# PD_Regulator.net
KiCad netlist of a schematic drawn in Altium Designer
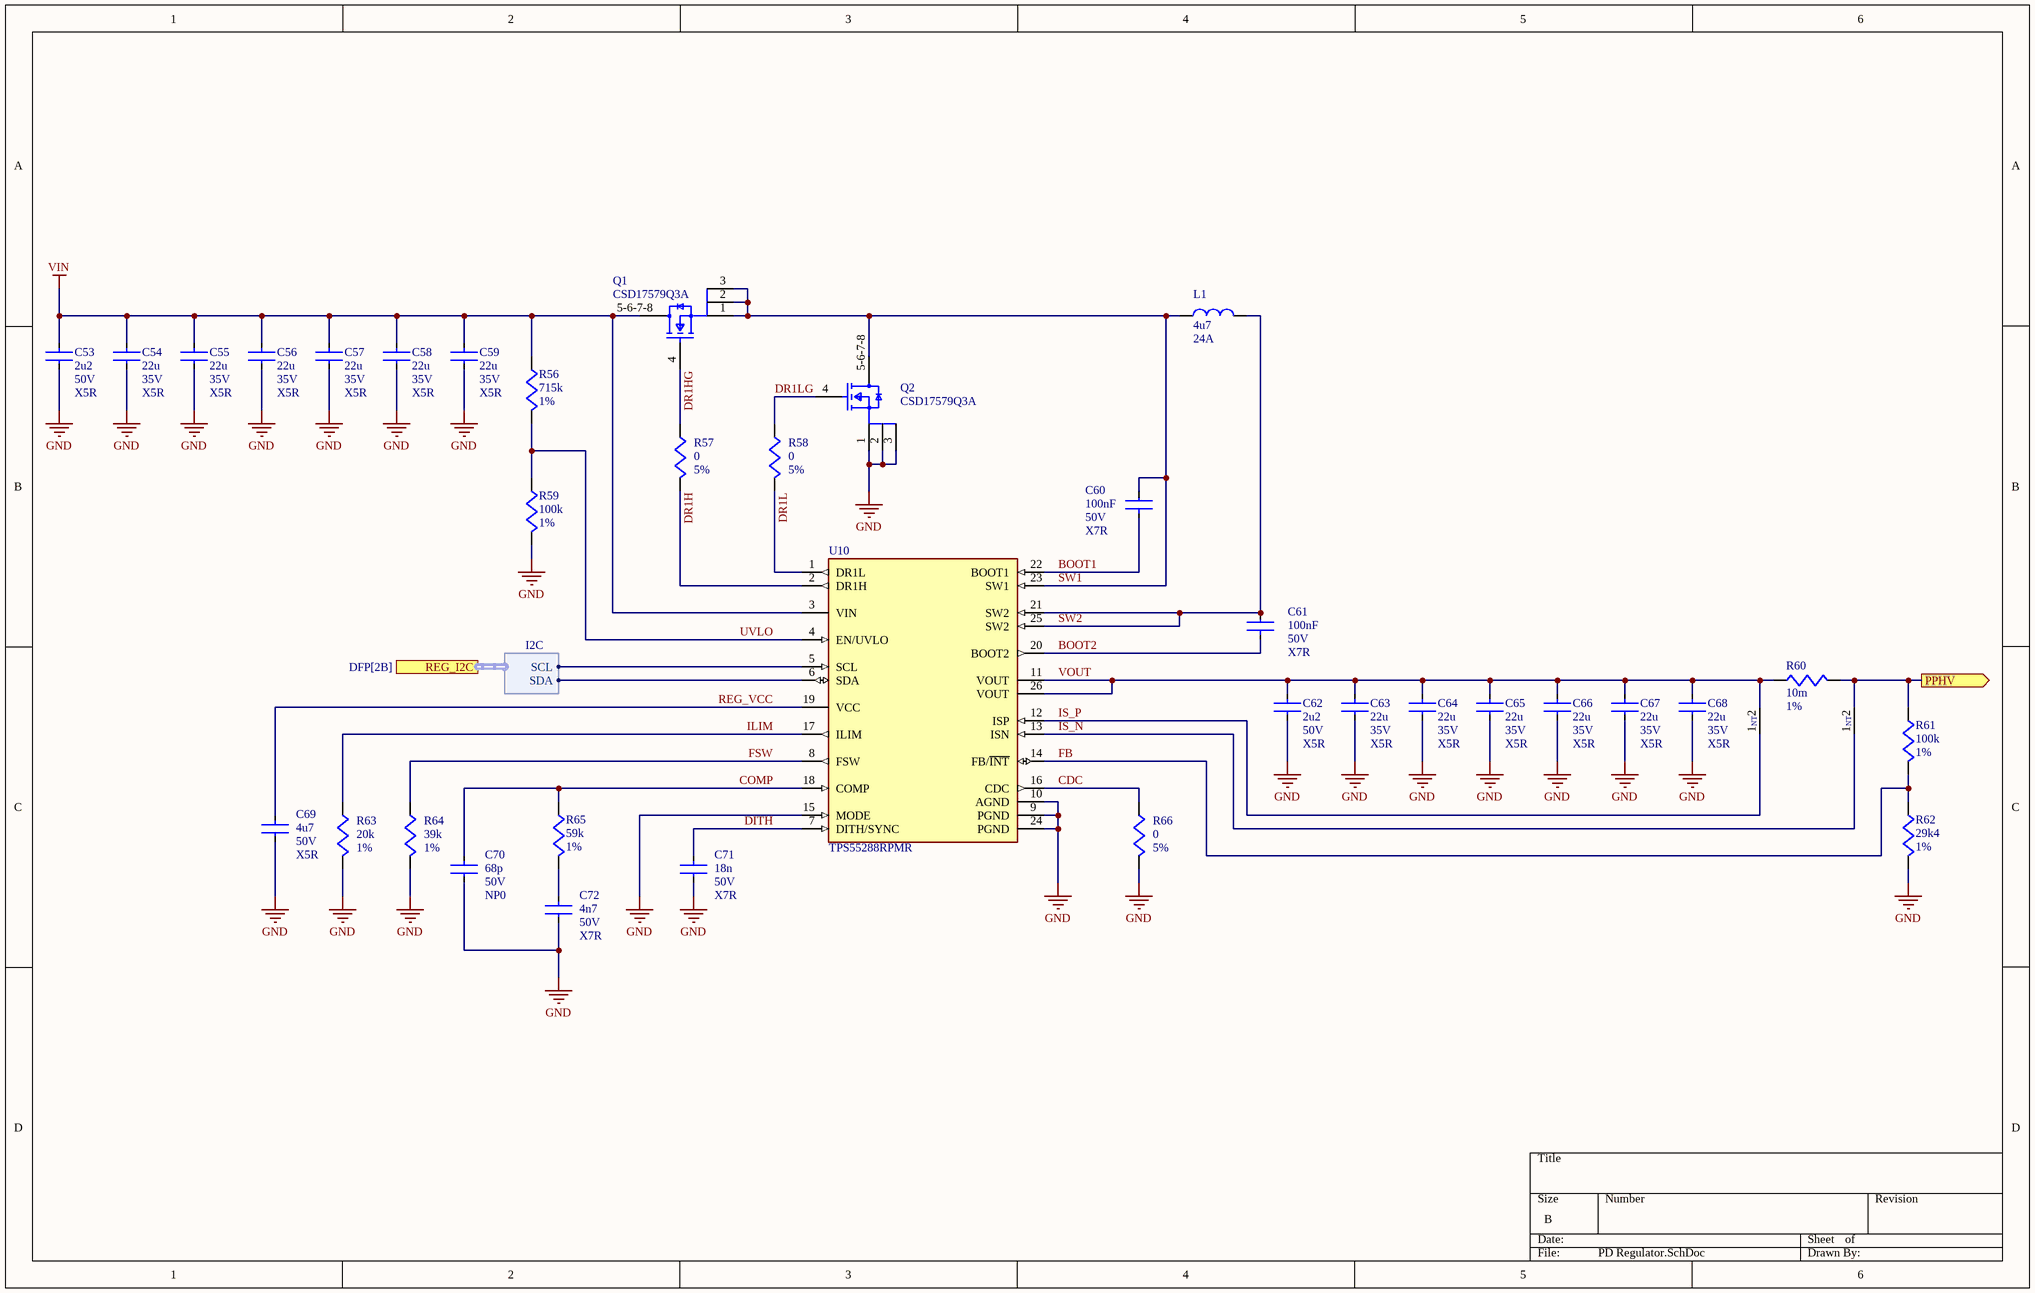
[diagram p0: PD Regulator.SchDoc]

(export (version "E")
  (design (tool "Eeschema 10.0.6"))
  (components
    (comp (ref "C53")
      (value "2u2")
      (footprint "CAPC2012X14N")
      (description "50V 2.2uF X5R ±10% 0805 Multilayer Ceramic Capacitors MLCC - SMD/SMT ROHS")
      (fields
        (field (name "VOLTAGE") "50V")
        (field (name "DIELECTRIC") "X5R")
        (field (name "LCSC PART #") "C377773")
        (field (name "Comment") "2.2uF 50V 0805")
      )
      (libsource (lib "CWRU Motorsports") (part "Capacitor"))
    )
    (comp (ref "C54")
      (value "22u")
      (footprint "CAPC3225X18N")
      (description "35V 22uF X5R ±20% 1210 Multilayer Ceramic Capacitors MLCC - SMD/SMT ROHS")
      (fields
        (field (name "VOLTAGE") "35V")
        (field (name "DIELECTRIC") "X5R")
        (field (name "LCSC PART #") "C778721")
        (field (name "Comment") "22uF 35V 1210 X5R")
      )
      (libsource (lib "CWRU Motorsports") (part "Capacitor"))
    )
    (comp (ref "C55")
      (value "22u")
      (footprint "CAPC3225X18N")
      (description "35V 22uF X5R ±20% 1210 Multilayer Ceramic Capacitors MLCC - SMD/SMT ROHS")
      (fields
        (field (name "VOLTAGE") "35V")
        (field (name "DIELECTRIC") "X5R")
        (field (name "LCSC PART #") "C778721")
        (field (name "Comment") "22uF 35V 1210 X5R")
      )
      (libsource (lib "CWRU Motorsports") (part "Capacitor"))
    )
    (comp (ref "C56")
      (value "22u")
      (footprint "CAPC3225X18N")
      (description "35V 22uF X5R ±20% 1210 Multilayer Ceramic Capacitors MLCC - SMD/SMT ROHS")
      (fields
        (field (name "VOLTAGE") "35V")
        (field (name "DIELECTRIC") "X5R")
        (field (name "LCSC PART #") "C778721")
        (field (name "Comment") "22uF 35V 1210 X5R")
      )
      (libsource (lib "CWRU Motorsports") (part "Capacitor"))
    )
    (comp (ref "C57")
      (value "22u")
      (footprint "CAPC3225X18N")
      (description "35V 22uF X5R ±20% 1210 Multilayer Ceramic Capacitors MLCC - SMD/SMT ROHS")
      (fields
        (field (name "VOLTAGE") "35V")
        (field (name "DIELECTRIC") "X5R")
        (field (name "LCSC PART #") "C778721")
        (field (name "Comment") "22uF 35V 1210 X5R")
      )
      (libsource (lib "CWRU Motorsports") (part "Capacitor"))
    )
    (comp (ref "C58")
      (value "22u")
      (footprint "CAPC3225X18N")
      (description "35V 22uF X5R ±20% 1210 Multilayer Ceramic Capacitors MLCC - SMD/SMT ROHS")
      (fields
        (field (name "VOLTAGE") "35V")
        (field (name "DIELECTRIC") "X5R")
        (field (name "LCSC PART #") "C778721")
        (field (name "Comment") "22uF 35V 1210 X5R")
      )
      (libsource (lib "CWRU Motorsports") (part "Capacitor"))
    )
    (comp (ref "C59")
      (value "22u")
      (footprint "CAPC3225X18N")
      (description "35V 22uF X5R ±20% 1210 Multilayer Ceramic Capacitors MLCC - SMD/SMT ROHS")
      (fields
        (field (name "VOLTAGE") "35V")
        (field (name "DIELECTRIC") "X5R")
        (field (name "LCSC PART #") "C778721")
        (field (name "Comment") "22uF 35V 1210 X5R")
      )
      (libsource (lib "CWRU Motorsports") (part "Capacitor"))
    )
    (comp (ref "C60")
      (value "100nF")
      (footprint "CAPC1608X08N")
      (description "50V 100nF X7R ±10% 0603 Multilayer Ceramic Capacitors MLCC - SMD/SMT ROHS")
      (fields
        (field (name "VOLTAGE") "50V")
        (field (name "DIELECTRIC") "X7R")
        (field (name "LCSC PART #") "C1591")
        (field (name "Comment") "100nF 50V X7R 0603")
      )
      (libsource (lib "CWRU Motorsports") (part "Capacitor"))
    )
    (comp (ref "C61")
      (value "100nF")
      (footprint "CAPC1608X08N")
      (description "50V 100nF X7R ±10% 0603 Multilayer Ceramic Capacitors MLCC - SMD/SMT ROHS")
      (fields
        (field (name "VOLTAGE") "50V")
        (field (name "DIELECTRIC") "X7R")
        (field (name "LCSC PART #") "C1591")
        (field (name "Comment") "100nF 50V X7R 0603")
      )
      (libsource (lib "CWRU Motorsports") (part "Capacitor"))
    )
    (comp (ref "C62")
      (value "2u2")
      (footprint "CAPC2012X14N")
      (description "50V 2.2uF X5R ±10% 0805 Multilayer Ceramic Capacitors MLCC - SMD/SMT ROHS")
      (fields
        (field (name "VOLTAGE") "50V")
        (field (name "DIELECTRIC") "X5R")
        (field (name "LCSC PART #") "C377773")
        (field (name "Comment") "2.2uF 50V 0805")
      )
      (libsource (lib "CWRU Motorsports") (part "Capacitor"))
    )
    (comp (ref "C63")
      (value "22u")
      (footprint "CAPC3225X18N")
      (description "35V 22uF X5R ±20% 1210 Multilayer Ceramic Capacitors MLCC - SMD/SMT ROHS")
      (fields
        (field (name "VOLTAGE") "35V")
        (field (name "DIELECTRIC") "X5R")
        (field (name "LCSC PART #") "C778721")
        (field (name "Comment") "22uF 35V 1210 X5R")
      )
      (libsource (lib "CWRU Motorsports") (part "Capacitor"))
    )
    (comp (ref "C64")
      (value "22u")
      (footprint "CAPC3225X18N")
      (description "35V 22uF X5R ±20% 1210 Multilayer Ceramic Capacitors MLCC - SMD/SMT ROHS")
      (fields
        (field (name "VOLTAGE") "35V")
        (field (name "DIELECTRIC") "X5R")
        (field (name "LCSC PART #") "C778721")
        (field (name "Comment") "22uF 35V 1210 X5R")
      )
      (libsource (lib "CWRU Motorsports") (part "Capacitor"))
    )
    (comp (ref "C65")
      (value "22u")
      (footprint "CAPC3225X18N")
      (description "35V 22uF X5R ±20% 1210 Multilayer Ceramic Capacitors MLCC - SMD/SMT ROHS")
      (fields
        (field (name "VOLTAGE") "35V")
        (field (name "DIELECTRIC") "X5R")
        (field (name "LCSC PART #") "C778721")
        (field (name "Comment") "22uF 35V 1210 X5R")
      )
      (libsource (lib "CWRU Motorsports") (part "Capacitor"))
    )
    (comp (ref "C66")
      (value "22u")
      (footprint "CAPC3225X18N")
      (description "35V 22uF X5R ±20% 1210 Multilayer Ceramic Capacitors MLCC - SMD/SMT ROHS")
      (fields
        (field (name "VOLTAGE") "35V")
        (field (name "DIELECTRIC") "X5R")
        (field (name "LCSC PART #") "C778721")
        (field (name "Comment") "22uF 35V 1210 X5R")
      )
      (libsource (lib "CWRU Motorsports") (part "Capacitor"))
    )
    (comp (ref "C67")
      (value "22u")
      (footprint "CAPC3225X18N")
      (description "35V 22uF X5R ±20% 1210 Multilayer Ceramic Capacitors MLCC - SMD/SMT ROHS")
      (fields
        (field (name "VOLTAGE") "35V")
        (field (name "DIELECTRIC") "X5R")
        (field (name "LCSC PART #") "C778721")
        (field (name "Comment") "22uF 35V 1210 X5R")
      )
      (libsource (lib "CWRU Motorsports") (part "Capacitor"))
    )
    (comp (ref "C68")
      (value "22u")
      (footprint "CAPC3225X18N")
      (description "35V 22uF X5R ±20% 1210 Multilayer Ceramic Capacitors MLCC - SMD/SMT ROHS")
      (fields
        (field (name "VOLTAGE") "35V")
        (field (name "DIELECTRIC") "X5R")
        (field (name "LCSC PART #") "C778721")
        (field (name "Comment") "22uF 35V 1210 X5R")
      )
      (libsource (lib "CWRU Motorsports") (part "Capacitor"))
    )
    (comp (ref "C69")
      (value "4u7")
      (footprint "CAPC2012X14N")
      (description "50V 4.7uF X5R ±10% 0805 Multilayer Ceramic Capacitors MLCC - SMD/SMT ROHS")
      (fields
        (field (name "VOLTAGE") "50V")
        (field (name "DIELECTRIC") "X5R")
        (field (name "LCSC PART #") "C98192")
        (field (name "Comment") "4.7uF 50V 0805")
      )
      (libsource (lib "CWRU Motorsports") (part "Capacitor"))
    )
    (comp (ref "C70")
      (value "68p")
      (footprint "CAPC1005X06N")
      (description "50V 68pF NP0 ±1% 0402 Multilayer Ceramic Capacitors MLCC - SMD/SMT ROHS")
      (fields
        (field (name "VOLTAGE") "50V")
        (field (name "DIELECTRIC") "NP0")
        (field (name "LCSC PART #") "C389103")
        (field (name "Comment") "68pF 50V 0402")
      )
      (libsource (lib "CWRU Motorsports") (part "Capacitor"))
    )
    (comp (ref "C71")
      (value "18n")
      (footprint "CAPC1005X06N")
      (description "50V 18nF X7R ±10% 0402 Multilayer Ceramic Capacitors MLCC - SMD/SMT ROHS")
      (fields
        (field (name "VOLTAGE") "50V")
        (field (name "DIELECTRIC") "X7R")
        (field (name "LCSC PART #") "C576740")
        (field (name "Comment") "18nF 50V 0402")
      )
      (libsource (lib "CWRU Motorsports") (part "Capacitor"))
    )
    (comp (ref "C72")
      (value "4n7")
      (footprint "CAPC1005X06N")
      (description "50V 4.7nF X7R ±10% 0402 Multilayer Ceramic Capacitors MLCC - SMD/SMT ROHS")
      (fields
        (field (name "VOLTAGE") "50V")
        (field (name "DIELECTRIC") "X7R")
        (field (name "LCSC PART #") "C1538")
        (field (name "Comment") "4.7nF 50V X7R 0402")
      )
      (libsource (lib "CWRU Motorsports") (part "Capacitor"))
    )
    (comp (ref "L1")
      (value "4u7")
      (footprint "INDP134126X58N")
      (description "20A 4.7uH Integrated molded inductor ±20% 24A SMD,12.6x13.5mm Power Inductors ROHS")
      (fields
        (field (name "SATURATION CURRENT") "24A")
        (field (name "LCSC PART #") "C526021")
        (field (name "Comment") "4.7uH 24A 20%")
      )
      (libsource (lib "CWRU Motorsports") (part "Inductor"))
    )
    (comp (ref "NT1")
      (value "8mil Net Tie")
      (footprint "Net Tie SMD-Footprint-1")
      (description "SMD Net Tie 8mil")
      (libsource (lib "CWRU Motorsports") (part "Net Tie"))
    )
    (comp (ref "NT2")
      (value "8mil Net Tie")
      (footprint "Net Tie SMD-Footprint-1")
      (description "SMD Net Tie 8mil")
      (libsource (lib "CWRU Motorsports") (part "Net Tie"))
    )
    (comp (ref "Q1")
      (value "CSD17579Q3A")
      (footprint "FP-DNH0008A-MFG")
      (description "MOSFET N-CH 30V 35A 8VSON")
      (fields (field (name "LCSC PART #") "C97376"))
      (libsource (lib "CWRU Motorsports") (part "2f22917ac7dd3b73ce0e75a3671b7f7"))
    )
    (comp (ref "Q2")
      (value "CSD17579Q3A")
      (footprint "FP-DNH0008A-MFG")
      (description "MOSFET N-CH 30V 35A 8VSON")
      (fields (field (name "LCSC PART #") "C97376"))
      (libsource (lib "CWRU Motorsports") (part "2f22917ac7dd3b73ce0e75a3671b7f7"))
    )
    (comp (ref "R56")
      (value "715k")
      (footprint "RESC1005X04M")
      (description "100mW Thick Film Resistors ±100ppm/℃ ±1% 715kΩ 0402 Chip Resistor - Surface Mount ROHS")
      (fields
        (field (name "TOLERANCE") "1%")
        (field (name "LCSC PART #") "C2480300")
        (field (name "Comment") "715k 1% 0402")
      )
      (libsource (lib "CWRU Motorsports") (part "Resistor"))
    )
    (comp (ref "R57")
      (value "0")
      (footprint "RESC1005X04M")
      (description "62.5mW Thick Film Resistors 50V ±5% 0Ω 0402 Chip Resistor - Surface Mount ROHS")
      (fields
        (field (name "TOLERANCE") "5%")
        (field (name "LCSC PART #") "C60485")
        (field (name "Comment") "0 Ohm 1% 0402")
      )
      (libsource (lib "CWRU Motorsports") (part "Resistor"))
    )
    (comp (ref "R58")
      (value "0")
      (footprint "RESC1005X04M")
      (description "62.5mW Thick Film Resistors 50V ±5% 0Ω 0402 Chip Resistor - Surface Mount ROHS")
      (fields
        (field (name "TOLERANCE") "5%")
        (field (name "LCSC PART #") "C60485")
        (field (name "Comment") "0 Ohm 1% 0402")
      )
      (libsource (lib "CWRU Motorsports") (part "Resistor"))
    )
    (comp (ref "R59")
      (value "100k")
      (footprint "RESC1005X04M")
      (description "62.5mW Thick Film Resistors 50V ±100ppm/℃ ±1% 100kΩ 0402 Chip Resistor - Surface Mount ROHS")
      (fields
        (field (name "TOLERANCE") "1%")
        (field (name "LCSC PART #") "C60491")
        (field (name "Comment") "100k 1% 0402")
      )
      (libsource (lib "CWRU Motorsports") (part "Resistor"))
    )
    (comp (ref "R60")
      (value "10m")
      (footprint "R1206")
      (description "1W 10mΩ ±70ppm/℃ ±1% 1206 Current Sense Resistors / Shunt Resistors ROHS")
      (fields
        (field (name "TOLERANCE") "1%")
        (field (name "LCSC PART #") "C105362")
        (field (name "Comment") "10m 1W 1% 1206")
      )
      (libsource (lib "CWRU Motorsports") (part "Resistor"))
    )
    (comp (ref "R61")
      (value "100k")
      (footprint "RESC1005X04M")
      (description "62.5mW Thick Film Resistors 50V ±100ppm/℃ ±1% 100kΩ 0402 Chip Resistor - Surface Mount ROHS")
      (fields
        (field (name "TOLERANCE") "1%")
        (field (name "LCSC PART #") "C60491")
        (field (name "Comment") "100k 1% 0402")
      )
      (libsource (lib "CWRU Motorsports") (part "Resistor"))
    )
    (comp (ref "R62")
      (value "29k4")
      (footprint "RESC1005X04M")
      (description "62.5mW Thick Film Resistors 50V ±100ppm/℃ ±1% 29.4kΩ 0402 Chip Resistor - Surface Mount ROHS")
      (fields
        (field (name "TOLERANCE") "1%")
        (field (name "LCSC PART #") "C26973")
        (field (name "Comment") "29k4 1% 0402")
      )
      (libsource (lib "CWRU Motorsports") (part "Resistor"))
    )
    (comp (ref "R63")
      (value "20k")
      (footprint "RESC1005X04M")
      (description "62.5mW Thick Film Resistors 50V ±100ppm/℃ ±1% 20kΩ 0402 Chip Resistor - Surface Mount ROHS")
      (fields
        (field (name "TOLERANCE") "1%")
        (field (name "LCSC PART #") "C93942")
        (field (name "Comment") "20k 0402 1%")
      )
      (libsource (lib "CWRU Motorsports") (part "Resistor"))
    )
    (comp (ref "R64")
      (value "39k")
      (footprint "RESC1005X04M")
      (description "62.5mW Thick Film Resistors 50V ±100ppm/℃ ±1% 39kΩ 0402 Chip Resistor - Surface Mount ROHS")
      (fields
        (field (name "TOLERANCE") "1%")
        (field (name "LCSC PART #") "C137995")
        (field (name "Comment") "39k 1% 0402")
      )
      (libsource (lib "CWRU Motorsports") (part "Resistor"))
    )
    (comp (ref "R65")
      (value "59k")
      (footprint "RESC1005X04M")
      (description "62.5mW Thick Film Resistors 50V ±100ppm/℃ ±1% 59kΩ 0402 Chip Resistor - Surface Mount ROHS")
      (fields
        (field (name "TOLERANCE") "1%")
        (field (name "LCSC PART #") "C163459")
        (field (name "Comment") "59k 1% 0402")
      )
      (libsource (lib "CWRU Motorsports") (part "Resistor"))
    )
    (comp (ref "R66")
      (value "0")
      (footprint "RESC1005X04M")
      (description "62.5mW Thick Film Resistors 50V ±5% 0Ω 0402 Chip Resistor - Surface Mount ROHS")
      (fields
        (field (name "TOLERANCE") "5%")
        (field (name "LCSC PART #") "C60485")
        (field (name "Comment") "0 Ohm 1% 0402")
      )
      (libsource (lib "CWRU Motorsports") (part "Resistor"))
    )
    (comp (ref "U10")
      (value "TPS55288RPMR")
      (footprint "FP-RPM0026A-MFG")
      (description "36V, 16A buck-boost converter with PPS control 26-VQFN-HR -40 to 150")
      (fields (field (name "LCSC PART #") "C2864583"))
      (libsource (lib "CWRU Motorsports") (part "c9cc6b36642bafa5d5669e6a5c22a1f"))
    )
  )
  (nets
    (net (code "2") (name "/BOOT1") (class "Default")
      (node (ref "C60") (pin "1") (pinfunction "1_1") (pintype "passive"))
      (node (ref "U10") (pin "22") (pinfunction "BOOT1_22") (pintype "input"))
    )
    (net (code "3") (name "/BOOT2") (class "Default")
      (node (ref "C61") (pin "1") (pinfunction "1_1") (pintype "passive"))
      (node (ref "U10") (pin "20") (pinfunction "BOOT2_20") (pintype "output"))
    )
    (net (code "4") (name "/CDC") (class "Default")
      (node (ref "R66") (pin "1") (pinfunction "1_1") (pintype "passive"))
      (node (ref "U10") (pin "16") (pinfunction "CDC_16") (pintype "output"))
    )
    (net (code "5") (name "/COMP") (class "Default")
      (node (ref "C70") (pin "1") (pinfunction "1_1") (pintype "passive"))
      (node (ref "R65") (pin "1") (pinfunction "1_1") (pintype "passive"))
      (node (ref "U10") (pin "18") (pinfunction "COMP_18") (pintype "input"))
    )
    (net (code "6") (name "/DITH") (class "Default")
      (node (ref "C71") (pin "1") (pinfunction "1_1") (pintype "passive"))
      (node (ref "U10") (pin "7") (pinfunction "DITH/SYNC_7") (pintype "input"))
    )
    (net (code "7") (name "/DR1H") (class "Default")
      (node (ref "R57") (pin "2") (pinfunction "2_2") (pintype "passive"))
      (node (ref "U10") (pin "2") (pinfunction "DR1H_2") (pintype "output"))
    )
    (net (code "8") (name "/DR1HG") (class "Default")
      (node (ref "Q1") (pin "4") (pinfunction "G_4") (pintype "passive"))
      (node (ref "R57") (pin "1") (pinfunction "1_1") (pintype "passive"))
    )
    (net (code "9") (name "/DR1L") (class "Default")
      (node (ref "R58") (pin "2") (pinfunction "2_2") (pintype "passive"))
      (node (ref "U10") (pin "1") (pinfunction "DR1L_1") (pintype "output"))
    )
    (net (code "10") (name "/DR1LG") (class "Default")
      (node (ref "Q2") (pin "4") (pinfunction "G_4") (pintype "passive"))
      (node (ref "R58") (pin "1") (pinfunction "1_1") (pintype "passive"))
    )
    (net (code "11") (name "/FB") (class "Default")
      (node (ref "R61") (pin "2") (pinfunction "2_2") (pintype "passive"))
      (node (ref "R62") (pin "1") (pinfunction "1_1") (pintype "passive"))
      (node (ref "U10") (pin "14") (pinfunction "FB/~{INT}_14") (pintype "bidirectional"))
    )
    (net (code "12") (name "/FSW") (class "Default")
      (node (ref "R64") (pin "1") (pinfunction "1_1") (pintype "passive"))
      (node (ref "U10") (pin "8") (pinfunction "FSW_8") (pintype "output"))
    )
    (net (code "13") (name "/ILIM") (class "Default")
      (node (ref "R63") (pin "1") (pinfunction "1_1") (pintype "passive"))
      (node (ref "U10") (pin "17") (pinfunction "ILIM_17") (pintype "output"))
    )
    (net (code "14") (name "/IS_N") (class "Default")
      (node (ref "NT1") (pin "1") (pinfunction "1_1") (pintype "passive"))
      (node (ref "U10") (pin "13") (pinfunction "ISN_13") (pintype "input"))
    )
    (net (code "15") (name "/IS_P") (class "Default")
      (node (ref "NT2") (pin "1") (pinfunction "1_1") (pintype "passive"))
      (node (ref "U10") (pin "12") (pinfunction "ISP_12") (pintype "input"))
    )
    (net (code "16") (name "/PPHV") (class "Default")
      (node (ref "NT1") (pin "2") (pinfunction "2_2") (pintype "passive"))
      (node (ref "R60") (pin "2") (pinfunction "2_2") (pintype "passive"))
      (node (ref "R61") (pin "1") (pinfunction "1_1") (pintype "passive"))
    )
    (net (code "17") (name "/REG_VCC") (class "Default")
      (node (ref "C69") (pin "1") (pinfunction "1_1") (pintype "passive"))
      (node (ref "U10") (pin "19") (pinfunction "VCC_19") (pintype "power_in"))
    )
    (net (code "18") (name "/SCL") (class "Default")
      (node (ref "U10") (pin "5") (pinfunction "SCL_5") (pintype "input"))
    )
    (net (code "19") (name "/SDA") (class "Default")
      (node (ref "U10") (pin "6") (pinfunction "SDA_6") (pintype "bidirectional"))
    )
    (net (code "20") (name "/SW1") (class "Default")
      (node (ref "C60") (pin "2") (pinfunction "2_2") (pintype "passive"))
      (node (ref "L1") (pin "1") (pinfunction "1_1") (pintype "passive"))
      (node (ref "Q1") (pin "1") (pinfunction "S_1") (pintype "passive"))
      (node (ref "Q1") (pin "2") (pinfunction "S_2") (pintype "passive"))
      (node (ref "Q1") (pin "3") (pinfunction "S_3") (pintype "passive"))
      (node (ref "Q2") (pin "5-6-7-8") (pinfunction "D_5-6-7-8") (pintype "passive"))
      (node (ref "U10") (pin "23") (pinfunction "SW1_23") (pintype "input"))
    )
    (net (code "21") (name "/SW2") (class "Default")
      (node (ref "C61") (pin "2") (pinfunction "2_2") (pintype "passive"))
      (node (ref "L1") (pin "2") (pinfunction "2_2") (pintype "passive"))
      (node (ref "U10") (pin "21") (pinfunction "SW2_21") (pintype "input"))
      (node (ref "U10") (pin "25") (pinfunction "SW2_25") (pintype "input"))
    )
    (net (code "22") (name "/UVLO") (class "Default")
      (node (ref "R56") (pin "2") (pinfunction "2_2") (pintype "passive"))
      (node (ref "R59") (pin "1") (pinfunction "1_1") (pintype "passive"))
      (node (ref "U10") (pin "4") (pinfunction "EN/UVLO_4") (pintype "input"))
    )
    (net (code "23") (name "/VOUT") (class "Default")
      (node (ref "C62") (pin "1") (pinfunction "1_1") (pintype "passive"))
      (node (ref "C63") (pin "1") (pinfunction "1_1") (pintype "passive"))
      (node (ref "C64") (pin "1") (pinfunction "1_1") (pintype "passive"))
      (node (ref "C65") (pin "1") (pinfunction "1_1") (pintype "passive"))
      (node (ref "C66") (pin "1") (pinfunction "1_1") (pintype "passive"))
      (node (ref "C67") (pin "1") (pinfunction "1_1") (pintype "passive"))
      (node (ref "C68") (pin "1") (pinfunction "1_1") (pintype "passive"))
      (node (ref "NT2") (pin "2") (pinfunction "2_2") (pintype "passive"))
      (node (ref "R60") (pin "1") (pinfunction "1_1") (pintype "passive"))
      (node (ref "U10") (pin "11") (pinfunction "VOUT_11") (pintype "power_in"))
      (node (ref "U10") (pin "26") (pinfunction "VOUT_26") (pintype "power_in"))
    )
    (net (code "25") (name "GND") (class "Default")
      (node (ref "C53") (pin "2") (pinfunction "2_2") (pintype "passive"))
      (node (ref "C54") (pin "2") (pinfunction "2_2") (pintype "passive"))
      (node (ref "C55") (pin "2") (pinfunction "2_2") (pintype "passive"))
      (node (ref "C56") (pin "2") (pinfunction "2_2") (pintype "passive"))
      (node (ref "C57") (pin "2") (pinfunction "2_2") (pintype "passive"))
      (node (ref "C58") (pin "2") (pinfunction "2_2") (pintype "passive"))
      (node (ref "C59") (pin "2") (pinfunction "2_2") (pintype "passive"))
      (node (ref "C62") (pin "2") (pinfunction "2_2") (pintype "passive"))
      (node (ref "C63") (pin "2") (pinfunction "2_2") (pintype "passive"))
      (node (ref "C64") (pin "2") (pinfunction "2_2") (pintype "passive"))
      (node (ref "C65") (pin "2") (pinfunction "2_2") (pintype "passive"))
      (node (ref "C66") (pin "2") (pinfunction "2_2") (pintype "passive"))
      (node (ref "C67") (pin "2") (pinfunction "2_2") (pintype "passive"))
      (node (ref "C68") (pin "2") (pinfunction "2_2") (pintype "passive"))
      (node (ref "C69") (pin "2") (pinfunction "2_2") (pintype "passive"))
      (node (ref "C70") (pin "2") (pinfunction "2_2") (pintype "passive"))
      (node (ref "C71") (pin "2") (pinfunction "2_2") (pintype "passive"))
      (node (ref "C72") (pin "2") (pinfunction "2_2") (pintype "passive"))
      (node (ref "Q2") (pin "1") (pinfunction "S_1") (pintype "passive"))
      (node (ref "Q2") (pin "2") (pinfunction "S_2") (pintype "passive"))
      (node (ref "Q2") (pin "3") (pinfunction "S_3") (pintype "passive"))
      (node (ref "R59") (pin "2") (pinfunction "2_2") (pintype "passive"))
      (node (ref "R62") (pin "2") (pinfunction "2_2") (pintype "passive"))
      (node (ref "R63") (pin "2") (pinfunction "2_2") (pintype "passive"))
      (node (ref "R64") (pin "2") (pinfunction "2_2") (pintype "passive"))
      (node (ref "R66") (pin "2") (pinfunction "2_2") (pintype "passive"))
      (node (ref "U10") (pin "10") (pinfunction "AGND_10") (pintype "power_in"))
      (node (ref "U10") (pin "15") (pinfunction "MODE_15") (pintype "input"))
      (node (ref "U10") (pin "24") (pinfunction "PGND_24") (pintype "power_in"))
      (node (ref "U10") (pin "9") (pinfunction "PGND_9") (pintype "power_in"))
    )
    (net (code "26") (name "Net-(C72-Pad1)") (class "Default")
      (node (ref "C72") (pin "1") (pinfunction "1_1") (pintype "passive"))
      (node (ref "R65") (pin "2") (pinfunction "2_2") (pintype "passive"))
    )
    (net (code "27") (name "VIN") (class "Default")
      (node (ref "C53") (pin "1") (pinfunction "1_1") (pintype "passive"))
      (node (ref "C54") (pin "1") (pinfunction "1_1") (pintype "passive"))
      (node (ref "C55") (pin "1") (pinfunction "1_1") (pintype "passive"))
      (node (ref "C56") (pin "1") (pinfunction "1_1") (pintype "passive"))
      (node (ref "C57") (pin "1") (pinfunction "1_1") (pintype "passive"))
      (node (ref "C58") (pin "1") (pinfunction "1_1") (pintype "passive"))
      (node (ref "C59") (pin "1") (pinfunction "1_1") (pintype "passive"))
      (node (ref "Q1") (pin "5-6-7-8") (pinfunction "D_5-6-7-8") (pintype "passive"))
      (node (ref "R56") (pin "1") (pinfunction "1_1") (pintype "passive"))
      (node (ref "U10") (pin "3") (pinfunction "VIN_3") (pintype "power_in"))
    )
  )
)
